# Whale_Engine-REVB_eagle.net
KiCad netlist of a schematic drawn in EAGLE
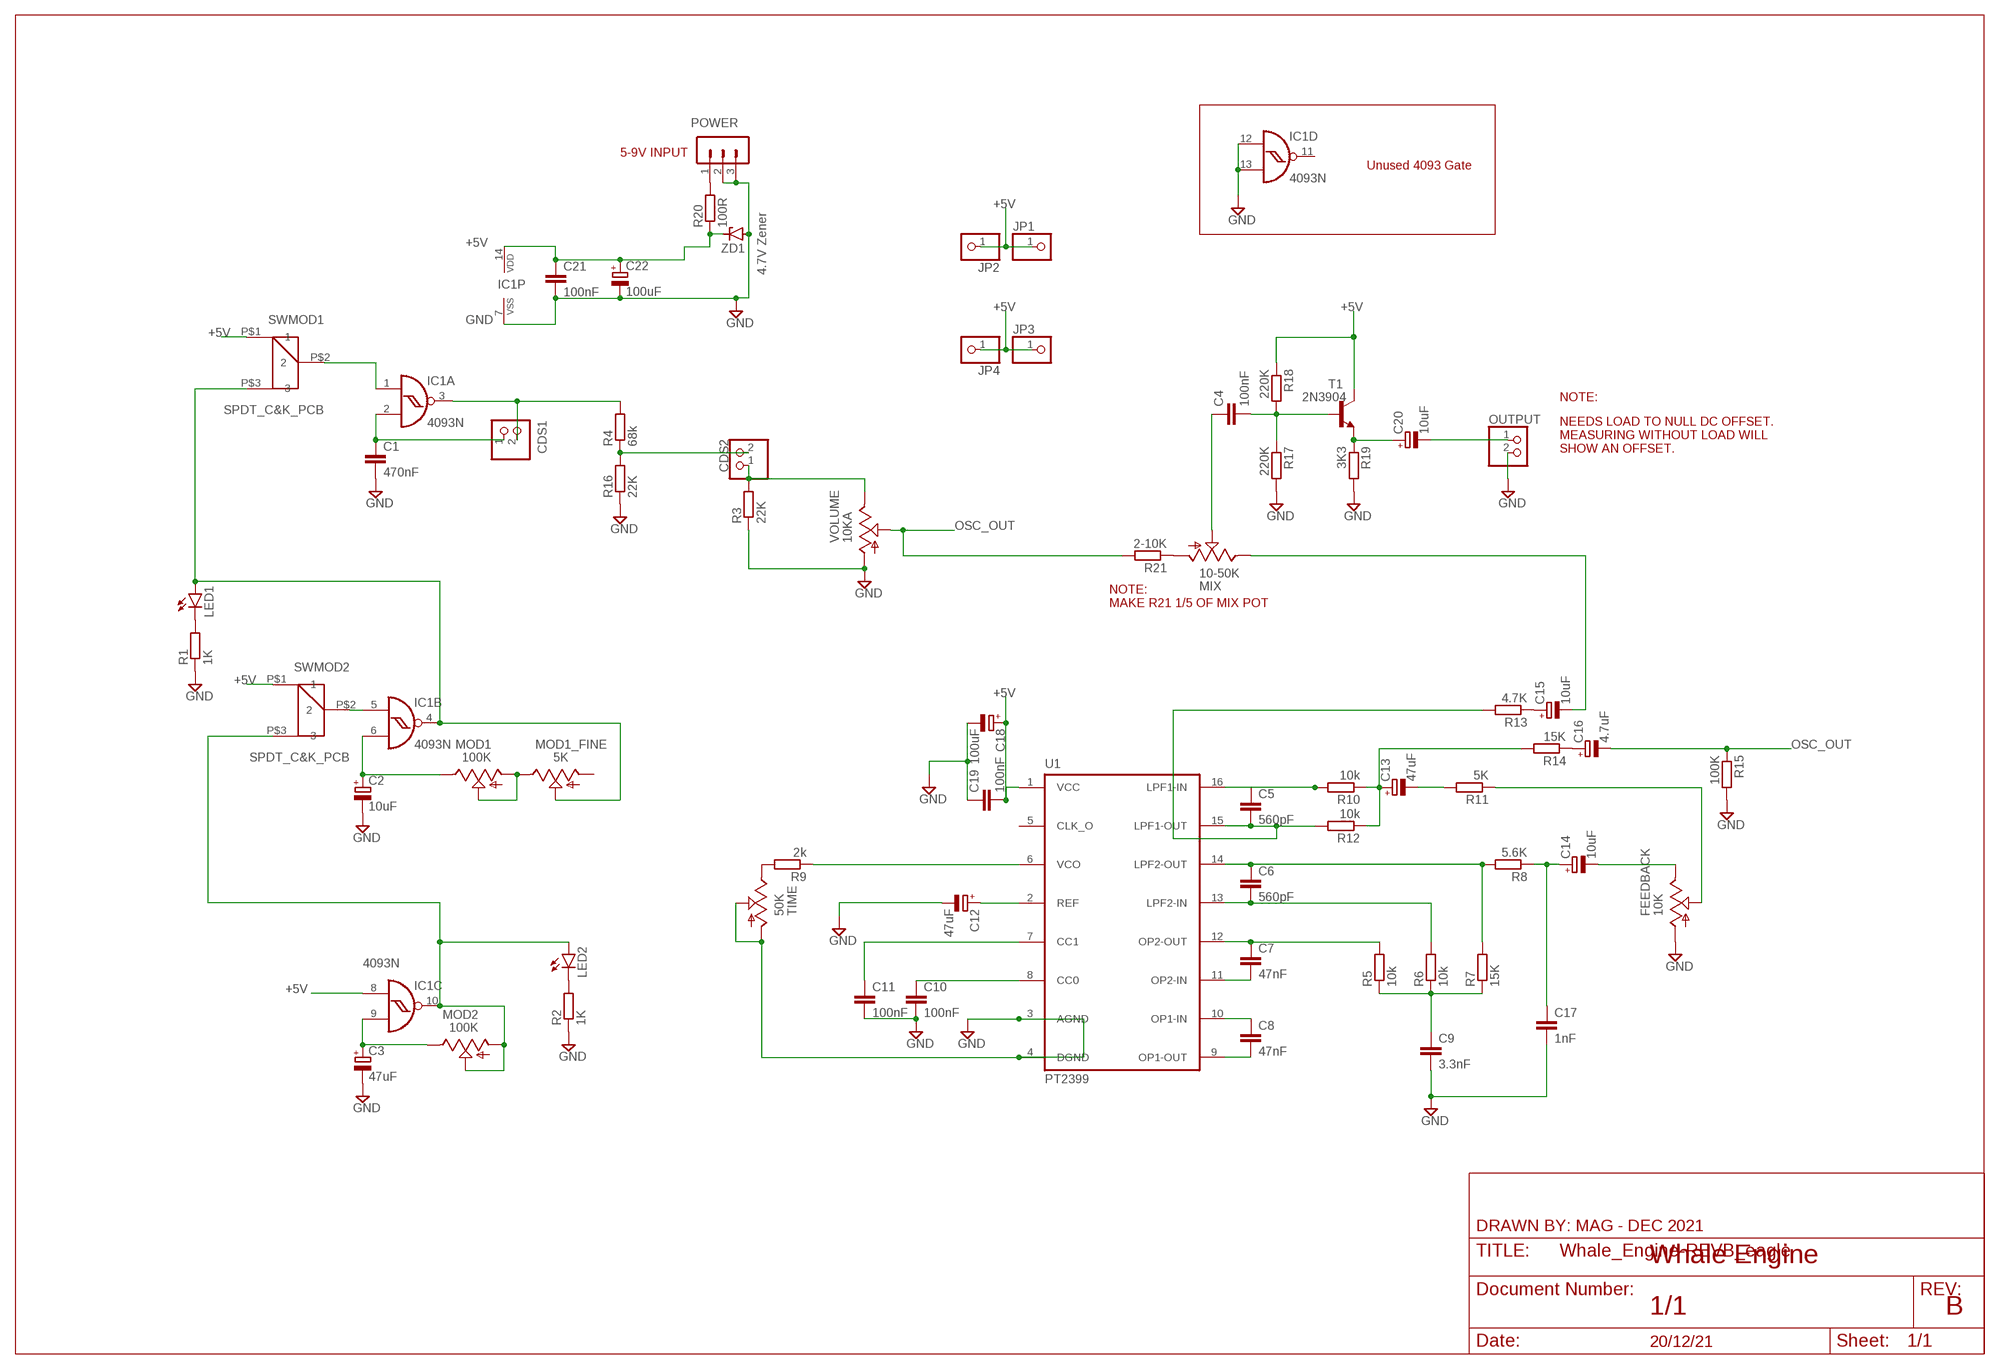
[diagram p0: schematic, sheet 1]

(export (version "E")
  (design (tool "Eeschema 10.0.6"))
  (components
    (comp (ref "C1")
      (value "470nF")
      (footprint "eagle-import:C7.5B3")
      (libsource (lib "eagle-import") (part "C7.5/3"))
    )
    (comp (ref "C2")
      (value "10uF")
      (footprint "eagle-import:E2-5")
      (libsource (lib "eagle-import") (part "CPOL-EUE2-5"))
    )
    (comp (ref "C3")
      (value "47uF")
      (footprint "eagle-import:E2-5")
      (libsource (lib "eagle-import") (part "CPOL-EUE2-5"))
    )
    (comp (ref "C4")
      (value "100nF")
      (footprint "eagle-import:C050-025X075")
      (libsource (lib "eagle-import") (part "C-EU050-025X075"))
    )
    (comp (ref "C5")
      (value "560pF")
      (footprint "eagle-import:C2.5-2")
      (libsource (lib "eagle-import") (part "C2.5/2"))
    )
    (comp (ref "C6")
      (value "560pF")
      (footprint "eagle-import:C2.5-2")
      (libsource (lib "eagle-import") (part "C2.5/2"))
    )
    (comp (ref "C7")
      (value "47nF")
      (footprint "eagle-import:C2.5-2")
      (libsource (lib "eagle-import") (part "C2.5/2"))
    )
    (comp (ref "C8")
      (value "47nF")
      (footprint "eagle-import:C2.5-2")
      (libsource (lib "eagle-import") (part "C2.5/2"))
    )
    (comp (ref "C9")
      (value "3.3nF")
      (footprint "eagle-import:C2.5-2")
      (libsource (lib "eagle-import") (part "C2.5/2"))
    )
    (comp (ref "C10")
      (value "100nF")
      (footprint "eagle-import:C2.5-2")
      (libsource (lib "eagle-import") (part "C2.5/2"))
    )
    (comp (ref "C11")
      (value "100nF")
      (footprint "eagle-import:C2.5-2")
      (libsource (lib "eagle-import") (part "C2.5/2"))
    )
    (comp (ref "C12")
      (value "47uF")
      (footprint "eagle-import:E2-5")
      (libsource (lib "eagle-import") (part "CPOL-EUE2-5"))
    )
    (comp (ref "C13")
      (value "47uF")
      (footprint "eagle-import:E2-5")
      (libsource (lib "eagle-import") (part "CPOL-EUE2-5"))
    )
    (comp (ref "C14")
      (value "10uF")
      (footprint "eagle-import:E2-5")
      (libsource (lib "eagle-import") (part "CPOL-EUE2-5"))
    )
    (comp (ref "C15")
      (value "10uF")
      (footprint "eagle-import:E2-5")
      (libsource (lib "eagle-import") (part "CPOL-EUE2-5"))
    )
    (comp (ref "C16")
      (value "4.7uF")
      (footprint "eagle-import:E2-5")
      (libsource (lib "eagle-import") (part "CPOL-EUE2-5"))
    )
    (comp (ref "C17")
      (value "1nF")
      (footprint "eagle-import:C2.5-2")
      (libsource (lib "eagle-import") (part "C2.5/2"))
    )
    (comp (ref "C18")
      (value "100uF")
      (footprint "eagle-import:E2-5")
      (libsource (lib "eagle-import") (part "CPOL-EUE2-5"))
    )
    (comp (ref "C19")
      (value "100nF")
      (footprint "eagle-import:C2.5-2")
      (libsource (lib "eagle-import") (part "C2.5/2"))
    )
    (comp (ref "C20")
      (value "10uF")
      (footprint "eagle-import:E2-5")
      (libsource (lib "eagle-import") (part "CPOL-EUE2-5"))
    )
    (comp (ref "C21")
      (value "100nF")
      (footprint "eagle-import:C2.5-2")
      (libsource (lib "eagle-import") (part "C2.5/2"))
    )
    (comp (ref "C22")
      (value "100uF")
      (footprint "eagle-import:E2-5")
      (libsource (lib "eagle-import") (part "CPOL-EUE2-5"))
    )
    (comp (ref "CDS1")
      (value "PINHD-1X2")
      (footprint "eagle-import:1X02")
      (libsource (lib "eagle-import") (part "PINHD-1X2"))
    )
    (comp (ref "CDS2")
      (value "PINHD-1X2")
      (footprint "eagle-import:1X02")
      (libsource (lib "eagle-import") (part "PINHD-1X2"))
    )
    (comp (ref "FEEDBACK")
      (value "10K")
      (footprint "eagle-import:9MM_SNAP-IN_POT")
      (libsource (lib "eagle-import") (part "9MM_SNAP-IN_POT_"))
    )
    (comp (ref "IC1")
      (value "4093N")
      (footprint "eagle-import:DIL14")
      (libsource (lib "eagle-import") (part "4093N"))
    )
    (comp (ref "JP1")
      (value "PINHD-1X1")
      (footprint "eagle-import:1X01")
      (libsource (lib "eagle-import") (part "PINHD-1X1"))
    )
    (comp (ref "JP2")
      (value "PINHD-1X1")
      (footprint "eagle-import:1X01")
      (libsource (lib "eagle-import") (part "PINHD-1X1"))
    )
    (comp (ref "JP3")
      (value "PINHD-1X1")
      (footprint "eagle-import:1X01")
      (libsource (lib "eagle-import") (part "PINHD-1X1"))
    )
    (comp (ref "JP4")
      (value "PINHD-1X1")
      (footprint "eagle-import:1X01")
      (libsource (lib "eagle-import") (part "PINHD-1X1"))
    )
    (comp (ref "LED1")
      (value "LED3MM")
      (footprint "eagle-import:LED3MM")
      (libsource (lib "eagle-import") (part "LED3MM"))
    )
    (comp (ref "LED2")
      (value "LED3MM")
      (footprint "eagle-import:LED3MM")
      (libsource (lib "eagle-import") (part "LED3MM"))
    )
    (comp (ref "MIX")
      (value "10-50K")
      (footprint "eagle-import:9MM_SNAP-IN_POT")
      (libsource (lib "eagle-import") (part "9MM_SNAP-IN_POT_"))
    )
    (comp (ref "MOD1")
      (value "100K")
      (footprint "eagle-import:9MM_SNAP-IN_POT")
      (libsource (lib "eagle-import") (part "9MM_SNAP-IN_POT_"))
    )
    (comp (ref "MOD1_FINE")
      (value "5K")
      (footprint "eagle-import:9MM_SNAP-IN_POT")
      (libsource (lib "eagle-import") (part "9MM_SNAP-IN_POT_"))
    )
    (comp (ref "MOD2")
      (value "100K")
      (footprint "eagle-import:9MM_SNAP-IN_POT")
      (libsource (lib "eagle-import") (part "9MM_SNAP-IN_POT_"))
    )
    (comp (ref "OUTPUT")
      (value "PINHD-1X2")
      (footprint "eagle-import:1X02")
      (libsource (lib "eagle-import") (part "PINHD-1X2"))
    )
    (comp (ref "POWER")
      (value "MA03-1")
      (footprint "eagle-import:MA03-1")
      (libsource (lib "eagle-import") (part "MA03-1"))
    )
    (comp (ref "R1")
      (value "1K")
      (footprint "eagle-import:0204_7")
      (libsource (lib "eagle-import") (part "R-EU_0204/7"))
    )
    (comp (ref "R2")
      (value "1K")
      (footprint "eagle-import:0204_7")
      (libsource (lib "eagle-import") (part "R-EU_0204/7"))
    )
    (comp (ref "R3")
      (value "22K")
      (footprint "eagle-import:0204_7")
      (libsource (lib "eagle-import") (part "R-EU_0204/7"))
    )
    (comp (ref "R4")
      (value "68k")
      (footprint "eagle-import:0204_7")
      (libsource (lib "eagle-import") (part "R-EU_0204/7"))
    )
    (comp (ref "R5")
      (value "10k")
      (footprint "eagle-import:0204_7")
      (libsource (lib "eagle-import") (part "R-EU_0204/7"))
    )
    (comp (ref "R6")
      (value "10k")
      (footprint "eagle-import:0204_7")
      (libsource (lib "eagle-import") (part "R-EU_0204/7"))
    )
    (comp (ref "R7")
      (value "15K")
      (footprint "eagle-import:0204_7")
      (libsource (lib "eagle-import") (part "R-EU_0204/7"))
    )
    (comp (ref "R8")
      (value "5.6K")
      (footprint "eagle-import:0204_7")
      (libsource (lib "eagle-import") (part "R-EU_0204/7"))
    )
    (comp (ref "R9")
      (value "2k")
      (footprint "eagle-import:0204_7")
      (libsource (lib "eagle-import") (part "R-EU_0204/7"))
    )
    (comp (ref "R10")
      (value "10k")
      (footprint "eagle-import:0204_7")
      (libsource (lib "eagle-import") (part "R-EU_0204/7"))
    )
    (comp (ref "R11")
      (value "5K")
      (footprint "eagle-import:0204_7")
      (libsource (lib "eagle-import") (part "R-EU_0204/7"))
    )
    (comp (ref "R12")
      (value "10k")
      (footprint "eagle-import:0204_7")
      (libsource (lib "eagle-import") (part "R-EU_0204/7"))
    )
    (comp (ref "R13")
      (value "4.7K")
      (footprint "eagle-import:0204_7")
      (libsource (lib "eagle-import") (part "R-EU_0204/7"))
    )
    (comp (ref "R14")
      (value "15K")
      (footprint "eagle-import:0204_7")
      (libsource (lib "eagle-import") (part "R-EU_0204/7"))
    )
    (comp (ref "R15")
      (value "100K")
      (footprint "eagle-import:0204_7")
      (libsource (lib "eagle-import") (part "R-EU_0204/7"))
    )
    (comp (ref "R16")
      (value "22K")
      (footprint "eagle-import:0204_7")
      (libsource (lib "eagle-import") (part "R-EU_0204/7"))
    )
    (comp (ref "R17")
      (value "220K")
      (footprint "eagle-import:0204_7")
      (libsource (lib "eagle-import") (part "R-EU_0204/7"))
    )
    (comp (ref "R18")
      (value "220K")
      (footprint "eagle-import:0204_7")
      (libsource (lib "eagle-import") (part "R-EU_0204/7"))
    )
    (comp (ref "R19")
      (value "3K3")
      (footprint "eagle-import:0204_7")
      (libsource (lib "eagle-import") (part "R-EU_0204/7"))
    )
    (comp (ref "R20")
      (value "100R")
      (footprint "eagle-import:0204_7")
      (libsource (lib "eagle-import") (part "R-EU_0204/7"))
    )
    (comp (ref "R21")
      (value "2-10K")
      (footprint "eagle-import:0204_7")
      (libsource (lib "eagle-import") (part "R-EU_0204/7"))
    )
    (comp (ref "SWMOD1")
      (value "SPDT_C&K_PCB")
      (footprint "eagle-import:C&K_SPDT_PCB")
      (libsource (lib "eagle-import") (part "SPDT_C&K_PCB"))
    )
    (comp (ref "SWMOD2")
      (value "SPDT_C&K_PCB")
      (footprint "eagle-import:C&K_SPDT_PCB")
      (libsource (lib "eagle-import") (part "SPDT_C&K_PCB"))
    )
    (comp (ref "T1")
      (value "2N3904")
      (footprint "eagle-import:TO92")
      (libsource (lib "eagle-import") (part "2N3904"))
    )
    (comp (ref "TIME")
      (value "50K")
      (footprint "eagle-import:9MM_SNAP-IN_POT")
      (libsource (lib "eagle-import") (part "9MM_SNAP-IN_POT_"))
    )
    (comp (ref "U1")
      (value "PT2399")
      (footprint "eagle-import:DIL16")
      (libsource (lib "eagle-import") (part "PT2399"))
    )
    (comp (ref "VOLUME")
      (value "10KA")
      (footprint "eagle-import:9MM_SNAP-IN_POT")
      (libsource (lib "eagle-import") (part "9MM_SNAP-IN_POT_"))
    )
    (comp (ref "ZD1")
      (value "4.7V Zener")
      (footprint "eagle-import:SOD81")
      (libsource (lib "eagle-import") (part "BZD23"))
    )
  )
  (nets
    (net (code "1") (name "/+5V") (class "Default")
      (node (ref "C18") (pin "+") (pinfunction "+_+") (pintype "passive"))
      (node (ref "C19") (pin "2") (pinfunction "2_2") (pintype "passive"))
      (node (ref "C21") (pin "1") (pinfunction "1_1") (pintype "passive"))
      (node (ref "C22") (pin "+") (pinfunction "+_+") (pintype "passive"))
      (node (ref "IC1") (pin "14") (pinfunction "VDD_14") (pintype "power_in"))
      (node (ref "IC1") (pin "8") (pinfunction "I0_8") (pintype "input"))
      (node (ref "JP1") (pin "1") (pinfunction "1_1") (pintype "passive"))
      (node (ref "JP2") (pin "1") (pinfunction "1_1") (pintype "passive"))
      (node (ref "JP3") (pin "1") (pinfunction "1_1") (pintype "passive"))
      (node (ref "JP4") (pin "1") (pinfunction "1_1") (pintype "passive"))
      (node (ref "R18") (pin "1") (pinfunction "1_1") (pintype "passive"))
      (node (ref "R20") (pin "1") (pinfunction "1_1") (pintype "passive"))
      (node (ref "SWMOD1") (pin "P$1") (pinfunction "1_P$1") (pintype "bidirectional"))
      (node (ref "SWMOD2") (pin "P$1") (pinfunction "1_P$1") (pintype "bidirectional"))
      (node (ref "T1") (pin "1") (pinfunction "C_1") (pintype "passive"))
      (node (ref "U1") (pin "1") (pinfunction "VCC_1") (pintype "power_in"))
      (node (ref "ZD1") (pin "C") (pinfunction "C_C") (pintype "passive"))
    )
    (net (code "2") (name "/OSC_OUT") (class "Default")
      (node (ref "C16") (pin "-") (pinfunction "-_-") (pintype "passive"))
      (node (ref "R15") (pin "1") (pinfunction "1_1") (pintype "passive"))
      (node (ref "R21") (pin "2") (pinfunction "2_2") (pintype "passive"))
      (node (ref "VOLUME") (pin "2") (pinfunction "S_2") (pintype "passive"))
    )
    (net (code "3") (name "GND") (class "Default")
      (node (ref "C1") (pin "2") (pinfunction "2_2") (pintype "passive"))
      (node (ref "C10") (pin "2") (pinfunction "2_2") (pintype "passive"))
      (node (ref "C11") (pin "2") (pinfunction "2_2") (pintype "passive"))
      (node (ref "C12") (pin "-") (pinfunction "-_-") (pintype "passive"))
      (node (ref "C17") (pin "2") (pinfunction "2_2") (pintype "passive"))
      (node (ref "C18") (pin "-") (pinfunction "-_-") (pintype "passive"))
      (node (ref "C19") (pin "1") (pinfunction "1_1") (pintype "passive"))
      (node (ref "C2") (pin "-") (pinfunction "-_-") (pintype "passive"))
      (node (ref "C21") (pin "2") (pinfunction "2_2") (pintype "passive"))
      (node (ref "C22") (pin "-") (pinfunction "-_-") (pintype "passive"))
      (node (ref "C3") (pin "-") (pinfunction "-_-") (pintype "passive"))
      (node (ref "C9") (pin "2") (pinfunction "2_2") (pintype "passive"))
      (node (ref "FEEDBACK") (pin "1") (pinfunction "A_1") (pintype "passive"))
      (node (ref "IC1") (pin "12") (pinfunction "I0_12") (pintype "input"))
      (node (ref "IC1") (pin "13") (pinfunction "I1_13") (pintype "input"))
      (node (ref "IC1") (pin "7") (pinfunction "VSS_7") (pintype "power_in"))
      (node (ref "OUTPUT") (pin "2") (pinfunction "2_2") (pintype "passive"))
      (node (ref "POWER") (pin "2") (pinfunction "2_2") (pintype "passive"))
      (node (ref "POWER") (pin "3") (pinfunction "3_3") (pintype "passive"))
      (node (ref "R1") (pin "1") (pinfunction "1_1") (pintype "passive"))
      (node (ref "R15") (pin "2") (pinfunction "2_2") (pintype "passive"))
      (node (ref "R16") (pin "1") (pinfunction "1_1") (pintype "passive"))
      (node (ref "R17") (pin "2") (pinfunction "2_2") (pintype "passive"))
      (node (ref "R19") (pin "2") (pinfunction "2_2") (pintype "passive"))
      (node (ref "R2") (pin "1") (pinfunction "1_1") (pintype "passive"))
      (node (ref "R3") (pin "1") (pinfunction "1_1") (pintype "passive"))
      (node (ref "TIME") (pin "1") (pinfunction "A_1") (pintype "passive"))
      (node (ref "TIME") (pin "2") (pinfunction "S_2") (pintype "passive"))
      (node (ref "U1") (pin "3") (pinfunction "AGND_3") (pintype "power_in"))
      (node (ref "U1") (pin "4") (pinfunction "DGND_4") (pintype "power_in"))
      (node (ref "VOLUME") (pin "1") (pinfunction "A_1") (pintype "passive"))
      (node (ref "ZD1") (pin "A") (pinfunction "A_A") (pintype "passive"))
    )
    (net (code "4") (name "Net-(C9-Pad1)") (class "Default")
      (node (ref "C9") (pin "1") (pinfunction "1_1") (pintype "passive"))
      (node (ref "R5") (pin "1") (pinfunction "1_1") (pintype "passive"))
      (node (ref "R6") (pin "1") (pinfunction "1_1") (pintype "passive"))
      (node (ref "R7") (pin "1") (pinfunction "1_1") (pintype "passive"))
    )
    (net (code "5") (name "Net-(C13-Pad+)") (class "Default")
      (node (ref "C13") (pin "+") (pinfunction "+_+") (pintype "passive"))
      (node (ref "R10") (pin "1") (pinfunction "1_1") (pintype "passive"))
      (node (ref "R12") (pin "1") (pinfunction "1_1") (pintype "passive"))
      (node (ref "R14") (pin "2") (pinfunction "2_2") (pintype "passive"))
    )
    (net (code "6") (name "Net-(C13-Pad-)") (class "Default")
      (node (ref "C13") (pin "-") (pinfunction "-_-") (pintype "passive"))
      (node (ref "R11") (pin "2") (pinfunction "2_2") (pintype "passive"))
    )
    (net (code "7") (name "Net-(C14-Pad+)") (class "Default")
      (node (ref "C14") (pin "+") (pinfunction "+_+") (pintype "passive"))
      (node (ref "C17") (pin "1") (pinfunction "1_1") (pintype "passive"))
      (node (ref "R8") (pin "1") (pinfunction "1_1") (pintype "passive"))
    )
    (net (code "8") (name "Net-(C15-Pad+)") (class "Default")
      (node (ref "C15") (pin "+") (pinfunction "+_+") (pintype "passive"))
      (node (ref "R13") (pin "1") (pinfunction "1_1") (pintype "passive"))
    )
    (net (code "9") (name "Net-(C16-Pad+)") (class "Default")
      (node (ref "C16") (pin "+") (pinfunction "+_+") (pintype "passive"))
      (node (ref "R14") (pin "1") (pinfunction "1_1") (pintype "passive"))
    )
    (net (code "10") (name "Net-(C20-Pad-)") (class "Default")
      (node (ref "C20") (pin "-") (pinfunction "-_-") (pintype "passive"))
      (node (ref "OUTPUT") (pin "1") (pinfunction "1_1") (pintype "passive"))
    )
    (net (code "11") (name "Net-(CDS2-Pad2)") (class "Default")
      (node (ref "CDS2") (pin "2") (pinfunction "2_2") (pintype "passive"))
      (node (ref "R16") (pin "2") (pinfunction "2_2") (pintype "passive"))
      (node (ref "R4") (pin "1") (pinfunction "1_1") (pintype "passive"))
    )
    (net (code "12") (name "Net-(FEEDBACK-E)") (class "Default")
      (node (ref "C14") (pin "-") (pinfunction "-_-") (pintype "passive"))
      (node (ref "FEEDBACK") (pin "3") (pinfunction "E_3") (pintype "passive"))
    )
    (net (code "13") (name "Net-(FEEDBACK-S)") (class "Default")
      (node (ref "FEEDBACK") (pin "2") (pinfunction "S_2") (pintype "passive"))
      (node (ref "R11") (pin "1") (pinfunction "1_1") (pintype "passive"))
    )
    (net (code "14") (name "Net-(IC1A-I0)") (class "Default")
      (node (ref "IC1") (pin "1") (pinfunction "I0_1") (pintype "input"))
      (node (ref "SWMOD1") (pin "P$2") (pinfunction "2_P$2") (pintype "bidirectional"))
    )
    (net (code "15") (name "Net-(IC1A-I1)") (class "Default")
      (node (ref "C1") (pin "1") (pinfunction "1_1") (pintype "passive"))
      (node (ref "CDS1") (pin "1") (pinfunction "1_1") (pintype "passive"))
      (node (ref "IC1") (pin "2") (pinfunction "I1_2") (pintype "input"))
    )
    (net (code "16") (name "Net-(IC1A-O)") (class "Default")
      (node (ref "CDS1") (pin "2") (pinfunction "2_2") (pintype "passive"))
      (node (ref "IC1") (pin "3") (pinfunction "O_3") (pintype "output"))
      (node (ref "R4") (pin "2") (pinfunction "2_2") (pintype "passive"))
    )
    (net (code "17") (name "Net-(IC1B-I0)") (class "Default")
      (node (ref "IC1") (pin "5") (pinfunction "I0_5") (pintype "input"))
      (node (ref "SWMOD2") (pin "P$2") (pinfunction "2_P$2") (pintype "bidirectional"))
    )
    (net (code "18") (name "Net-(IC1B-I1)") (class "Default")
      (node (ref "C2") (pin "+") (pinfunction "+_+") (pintype "passive"))
      (node (ref "IC1") (pin "6") (pinfunction "I1_6") (pintype "input"))
      (node (ref "MOD1") (pin "3") (pinfunction "E_3") (pintype "passive"))
    )
    (net (code "19") (name "Net-(IC1B-O)") (class "Default")
      (node (ref "IC1") (pin "4") (pinfunction "O_4") (pintype "output"))
      (node (ref "LED1") (pin "A") (pinfunction "A_A") (pintype "passive"))
      (node (ref "MOD1_FINE") (pin "2") (pinfunction "S_2") (pintype "passive"))
      (node (ref "SWMOD1") (pin "P$3") (pinfunction "3_P$3") (pintype "bidirectional"))
    )
    (net (code "20") (name "Net-(IC1C-I1)") (class "Default")
      (node (ref "C3") (pin "+") (pinfunction "+_+") (pintype "passive"))
      (node (ref "IC1") (pin "9") (pinfunction "I1_9") (pintype "input"))
      (node (ref "MOD2") (pin "3") (pinfunction "E_3") (pintype "passive"))
    )
    (net (code "21") (name "Net-(IC1C-O)") (class "Default")
      (node (ref "IC1") (pin "10") (pinfunction "O_10") (pintype "output"))
      (node (ref "LED2") (pin "A") (pinfunction "A_A") (pintype "passive"))
      (node (ref "MOD2") (pin "1") (pinfunction "A_1") (pintype "passive"))
      (node (ref "MOD2") (pin "2") (pinfunction "S_2") (pintype "passive"))
      (node (ref "SWMOD2") (pin "P$3") (pinfunction "3_P$3") (pintype "bidirectional"))
    )
    (net (code "22") (name "Net-(LED1-C)") (class "Default")
      (node (ref "LED1") (pin "K") (pinfunction "C_K") (pintype "passive"))
      (node (ref "R1") (pin "2") (pinfunction "2_2") (pintype "passive"))
    )
    (net (code "23") (name "Net-(LED2-C)") (class "Default")
      (node (ref "LED2") (pin "K") (pinfunction "C_K") (pintype "passive"))
      (node (ref "R2") (pin "2") (pinfunction "2_2") (pintype "passive"))
    )
    (net (code "24") (name "Net-(MIX-A)") (class "Default")
      (node (ref "MIX") (pin "1") (pinfunction "A_1") (pintype "passive"))
      (node (ref "R21") (pin "1") (pinfunction "1_1") (pintype "passive"))
    )
    (net (code "25") (name "Net-(MIX-E)") (class "Default")
      (node (ref "C15") (pin "-") (pinfunction "-_-") (pintype "passive"))
      (node (ref "MIX") (pin "3") (pinfunction "E_3") (pintype "passive"))
    )
    (net (code "26") (name "Net-(MIX-S)") (class "Default")
      (node (ref "C4") (pin "1") (pinfunction "1_1") (pintype "passive"))
      (node (ref "MIX") (pin "2") (pinfunction "S_2") (pintype "passive"))
    )
    (net (code "27") (name "Net-(MOD1-A)") (class "Default")
      (node (ref "MOD1") (pin "1") (pinfunction "A_1") (pintype "passive"))
      (node (ref "MOD1") (pin "2") (pinfunction "S_2") (pintype "passive"))
      (node (ref "MOD1_FINE") (pin "3") (pinfunction "E_3") (pintype "passive"))
    )
    (net (code "28") (name "Net-(POWER-Pad1)") (class "Default")
      (node (ref "POWER") (pin "1") (pinfunction "1_1") (pintype "passive"))
      (node (ref "R20") (pin "2") (pinfunction "2_2") (pintype "passive"))
    )
    (net (code "29") (name "Net-(T1-B)") (class "Default")
      (node (ref "C4") (pin "2") (pinfunction "2_2") (pintype "passive"))
      (node (ref "R17") (pin "1") (pinfunction "1_1") (pintype "passive"))
      (node (ref "R18") (pin "2") (pinfunction "2_2") (pintype "passive"))
      (node (ref "T1") (pin "2") (pinfunction "B_2") (pintype "passive"))
    )
    (net (code "30") (name "Net-(T1-E)") (class "Default")
      (node (ref "C20") (pin "+") (pinfunction "+_+") (pintype "passive"))
      (node (ref "R19") (pin "1") (pinfunction "1_1") (pintype "passive"))
      (node (ref "T1") (pin "3") (pinfunction "E_3") (pintype "passive"))
    )
    (net (code "31") (name "Net-(TIME-E)") (class "Default")
      (node (ref "R9") (pin "2") (pinfunction "2_2") (pintype "passive"))
      (node (ref "TIME") (pin "3") (pinfunction "E_3") (pintype "passive"))
    )
    (net (code "32") (name "Net-(U1-CC0)") (class "Default")
      (node (ref "C10") (pin "1") (pinfunction "1_1") (pintype "passive"))
      (node (ref "U1") (pin "8") (pinfunction "CC0_8") (pintype "input"))
    )
    (net (code "33") (name "Net-(U1-CC1)") (class "Default")
      (node (ref "C11") (pin "1") (pinfunction "1_1") (pintype "passive"))
      (node (ref "U1") (pin "7") (pinfunction "CC1_7") (pintype "input"))
    )
    (net (code "34") (name "Net-(U1-LPF1-IN)") (class "Default")
      (node (ref "C5") (pin "1") (pinfunction "1_1") (pintype "passive"))
      (node (ref "R10") (pin "2") (pinfunction "2_2") (pintype "passive"))
      (node (ref "U1") (pin "16") (pinfunction "LPF1-IN_16") (pintype "input"))
    )
    (net (code "35") (name "Net-(U1-LPF1-OUT)") (class "Default")
      (node (ref "C5") (pin "2") (pinfunction "2_2") (pintype "passive"))
      (node (ref "R12") (pin "2") (pinfunction "2_2") (pintype "passive"))
      (node (ref "R13") (pin "2") (pinfunction "2_2") (pintype "passive"))
      (node (ref "U1") (pin "15") (pinfunction "LPF1-OUT_15") (pintype "output"))
    )
    (net (code "36") (name "Net-(U1-LPF2-IN)") (class "Default")
      (node (ref "C6") (pin "2") (pinfunction "2_2") (pintype "passive"))
      (node (ref "R6") (pin "2") (pinfunction "2_2") (pintype "passive"))
      (node (ref "U1") (pin "13") (pinfunction "LPF2-IN_13") (pintype "input"))
    )
    (net (code "37") (name "Net-(U1-LPF2-OUT)") (class "Default")
      (node (ref "C6") (pin "1") (pinfunction "1_1") (pintype "passive"))
      (node (ref "R7") (pin "2") (pinfunction "2_2") (pintype "passive"))
      (node (ref "R8") (pin "2") (pinfunction "2_2") (pintype "passive"))
      (node (ref "U1") (pin "14") (pinfunction "LPF2-OUT_14") (pintype "output"))
    )
    (net (code "38") (name "Net-(U1-OP1-IN)") (class "Default")
      (node (ref "C8") (pin "1") (pinfunction "1_1") (pintype "passive"))
      (node (ref "U1") (pin "10") (pinfunction "OP1-IN_10") (pintype "input"))
    )
    (net (code "39") (name "Net-(U1-OP1-OUT)") (class "Default")
      (node (ref "C8") (pin "2") (pinfunction "2_2") (pintype "passive"))
      (node (ref "U1") (pin "9") (pinfunction "OP1-OUT_9") (pintype "output"))
    )
    (net (code "40") (name "Net-(U1-OP2-IN)") (class "Default")
      (node (ref "C7") (pin "2") (pinfunction "2_2") (pintype "passive"))
      (node (ref "U1") (pin "11") (pinfunction "OP2-IN_11") (pintype "input"))
    )
    (net (code "41") (name "Net-(U1-OP2-OUT)") (class "Default")
      (node (ref "C7") (pin "1") (pinfunction "1_1") (pintype "passive"))
      (node (ref "R5") (pin "2") (pinfunction "2_2") (pintype "passive"))
      (node (ref "U1") (pin "12") (pinfunction "OP2-OUT_12") (pintype "output"))
    )
    (net (code "42") (name "Net-(U1-REF)") (class "Default")
      (node (ref "C12") (pin "+") (pinfunction "+_+") (pintype "passive"))
      (node (ref "U1") (pin "2") (pinfunction "REF_2") (pintype "input"))
    )
    (net (code "43") (name "Net-(U1-VCO)") (class "Default")
      (node (ref "R9") (pin "1") (pinfunction "1_1") (pintype "passive"))
      (node (ref "U1") (pin "6") (pinfunction "VCO_6") (pintype "input"))
    )
    (net (code "44") (name "Net-(VOLUME-E)") (class "Default")
      (node (ref "CDS2") (pin "1") (pinfunction "1_1") (pintype "passive"))
      (node (ref "R3") (pin "2") (pinfunction "2_2") (pintype "passive"))
      (node (ref "VOLUME") (pin "3") (pinfunction "E_3") (pintype "passive"))
    )
    (net (code "45") (name "unconnected-(IC1D-O-Pad11)") (class "Default")
      (node (ref "IC1") (pin "11") (pinfunction "O_11") (pintype "output"))
    )
    (net (code "46") (name "unconnected-(MOD1_FINE-A-Pad1)") (class "Default")
      (node (ref "MOD1_FINE") (pin "1") (pinfunction "A_1") (pintype "passive"))
    )
    (net (code "47") (name "unconnected-(U1-CLK_O-Pad5)") (class "Default")
      (node (ref "U1") (pin "5") (pinfunction "CLK_O_5") (pintype "output"))
    )
  )
)
